# Pack_Interface.net
KiCad netlist of a schematic drawn in Altium Designer
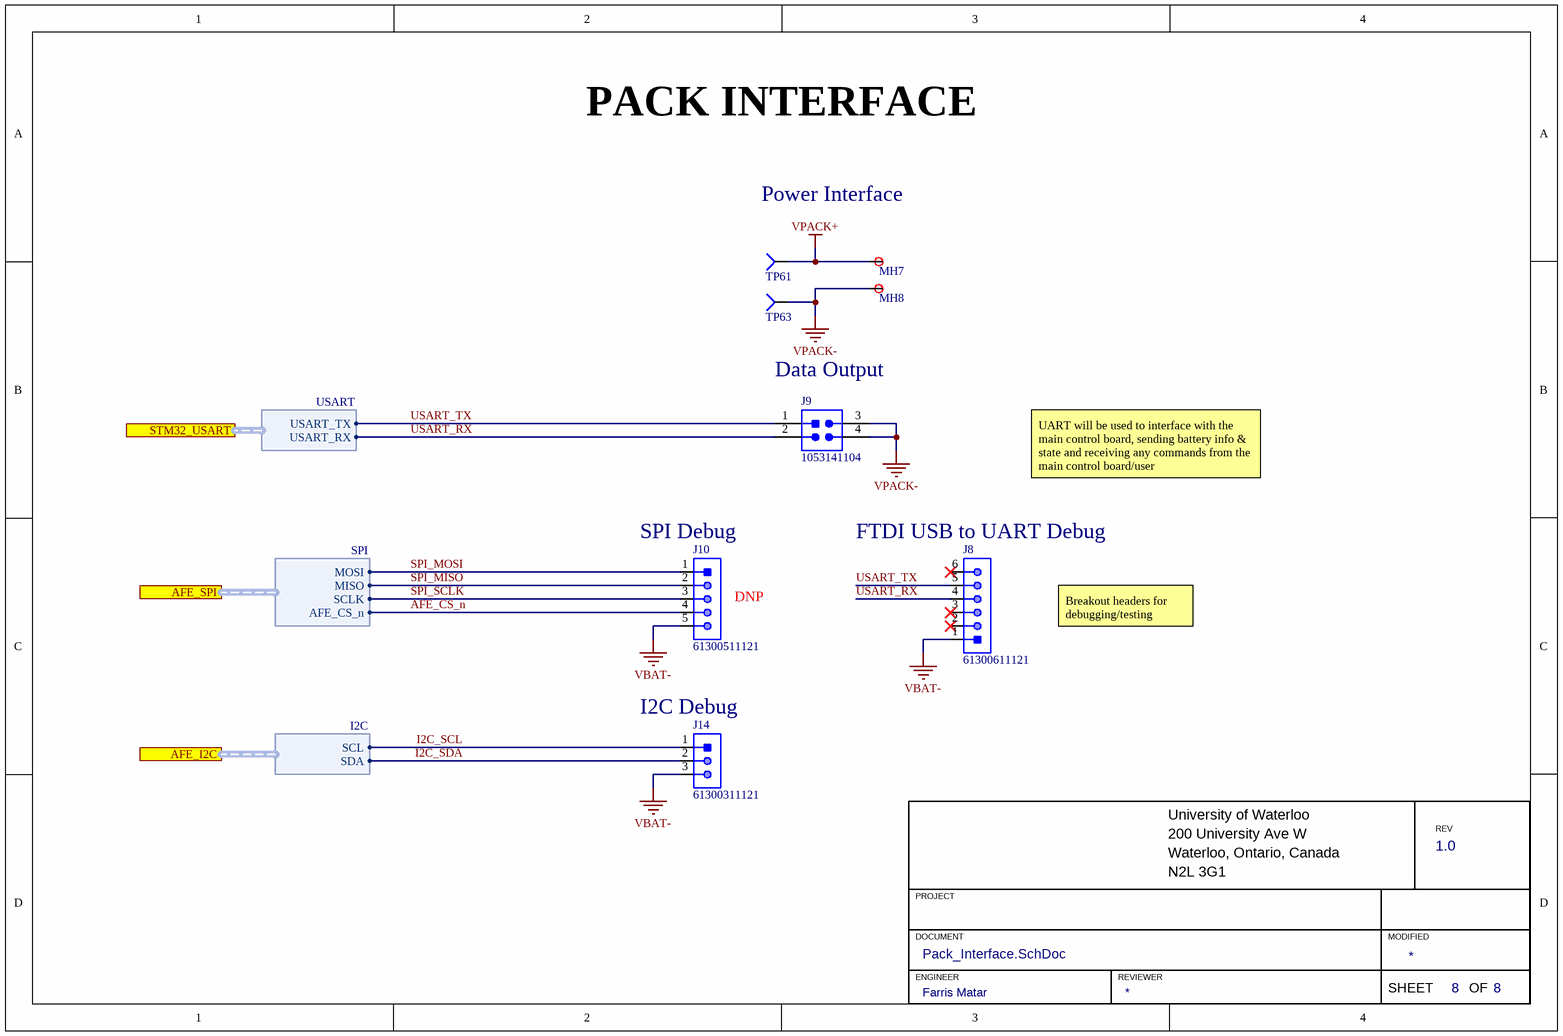
[diagram p0: Pack_Interface.SchDoc]

(export (version "E")
  (design (tool "Eeschema 10.0.6"))
  (components
    (comp (ref "J8")
      (value "HEADER 6x1")
      (footprint "HDR1X6")
      (description "CONN HEADER VERT 6POS 2.54MM")
      (fields (field (name "MANUFACTURER PART NUMBER 1") "61300611121"))
      (libsource (lib "Personal_Schematic_Library_2022") (part "HEADER 6x1"))
    )
    (comp (ref "J9")
      (value "0430450412")
      (footprint "MOLEX-NANOFIT 2x2 THRA")
      (description "CONN HEADER R/A 4POS 2.5MM")
      (fields (field (name "MANUFACTURER PART NUMBER 1") "1053141104"))
      (libsource (lib "Personal_Schematic_Library_2022") (part "CON_MOLEX-NANOFIT_2x2_THRA"))
    )
    (comp (ref "J10")
      (value "HEADER 5x1")
      (footprint "HDR1X5")
      (description "CONN HEADER VERT 5POS 2.54MM")
      (fields (field (name "MANUFACTURER PART NUMBER 1") "61300511121"))
      (libsource (lib "Personal_Schematic_Library_2022") (part "HEADER 5x1"))
    )
    (comp (ref "J14")
      (value "HEADER 3x1")
      (footprint "HDR1X3")
      (description "CONN HEADER VERT 3POS 2.54MM")
      (fields (field (name "MANUFACTURER PART NUMBER 1") "61300311121"))
      (libsource (lib "Personal_Schematic_Library_2022") (part "HEADER 3x1"))
    )
    (comp (ref "MH7")
      (value "MOUNTING_HOLE_M5")
      (footprint "MOUNTING_HOLE_5mm")
      (libsource (lib "Personal_Schematic_Library_2022") (part "MOUNTING_HOLE_M5"))
    )
    (comp (ref "MH8")
      (value "MOUNTING_HOLE_M5")
      (footprint "MOUNTING_HOLE_5mm")
      (libsource (lib "Personal_Schematic_Library_2022") (part "MOUNTING_HOLE_M5"))
    )
    (comp (ref "TP61")
      (value "TESTPOINT_SMD_LOOP")
      (footprint "S1751-46R")
      (description "TESTPOINT SMD LOOP")
      (libsource (lib "UWRT_Schematic_Library_2020") (part "TESTPOINT_SMD_LOOP"))
    )
    (comp (ref "TP63")
      (value "TESTPOINT_SMD_LOOP")
      (footprint "S1751-46R")
      (description "TESTPOINT SMD LOOP")
      (libsource (lib "UWRT_Schematic_Library_2020") (part "TESTPOINT_SMD_LOOP"))
    )
  )
  (nets
    (net (code "4") (name "/AFE_CS_n") (class "Default")
      (node (ref "J10") (pin "4") (pinfunction "4_4") (pintype "passive"))
    )
    (net (code "5") (name "/I2C_SCL") (class "Default")
      (node (ref "J14") (pin "1") (pinfunction "1_1") (pintype "passive"))
    )
    (net (code "6") (name "/I2C_SDA") (class "Default")
      (node (ref "J14") (pin "2") (pinfunction "2_2") (pintype "passive"))
    )
    (net (code "7") (name "/SPI_MISO") (class "Default")
      (node (ref "J10") (pin "2") (pinfunction "2_2") (pintype "passive"))
    )
    (net (code "8") (name "/SPI_MOSI") (class "Default")
      (node (ref "J10") (pin "1") (pinfunction "1_1") (pintype "passive"))
    )
    (net (code "9") (name "/SPI_SCLK") (class "Default")
      (node (ref "J10") (pin "3") (pinfunction "3_3") (pintype "passive"))
    )
    (net (code "10") (name "/USART_RX") (class "Default")
      (node (ref "J8") (pin "4") (pinfunction "4_4") (pintype "passive"))
      (node (ref "J9") (pin "2") (pinfunction "2_2") (pintype "passive"))
    )
    (net (code "11") (name "/USART_TX") (class "Default")
      (node (ref "J8") (pin "5") (pinfunction "5_5") (pintype "passive"))
      (node (ref "J9") (pin "1") (pinfunction "1_1") (pintype "passive"))
    )
    (net (code "15") (name "VBAT-") (class "Default")
      (node (ref "J10") (pin "5") (pinfunction "5_5") (pintype "passive"))
      (node (ref "J14") (pin "3") (pinfunction "3_3") (pintype "passive"))
      (node (ref "J8") (pin "1") (pinfunction "1_1") (pintype "passive"))
    )
    (net (code "16") (name "VPACK+") (class "Default")
      (node (ref "MH7") (pin "0") (pinfunction "0_0") (pintype "passive"))
      (node (ref "TP61") (pin "1") (pinfunction "=value_1") (pintype "passive"))
    )
    (net (code "17") (name "VPACK-") (class "Default")
      (node (ref "J9") (pin "3") (pinfunction "3_3") (pintype "passive"))
      (node (ref "J9") (pin "4") (pinfunction "4_4") (pintype "passive"))
      (node (ref "MH8") (pin "0") (pinfunction "0_0") (pintype "passive"))
      (node (ref "TP63") (pin "1") (pinfunction "=value_1") (pintype "passive"))
    )
    (net (code "18") (name "unconnected-(J8-Pad2)") (class "Default")
      (node (ref "J8") (pin "2") (pinfunction "2_2") (pintype "passive+no_connect"))
    )
    (net (code "19") (name "unconnected-(J8-Pad3)") (class "Default")
      (node (ref "J8") (pin "3") (pinfunction "3_3") (pintype "passive+no_connect"))
    )
    (net (code "20") (name "unconnected-(J8-Pad6)") (class "Default")
      (node (ref "J8") (pin "6") (pinfunction "6_6") (pintype "passive+no_connect"))
    )
  )
)
